# Filter2.net
KiCad netlist of a schematic drawn in Altium Designer
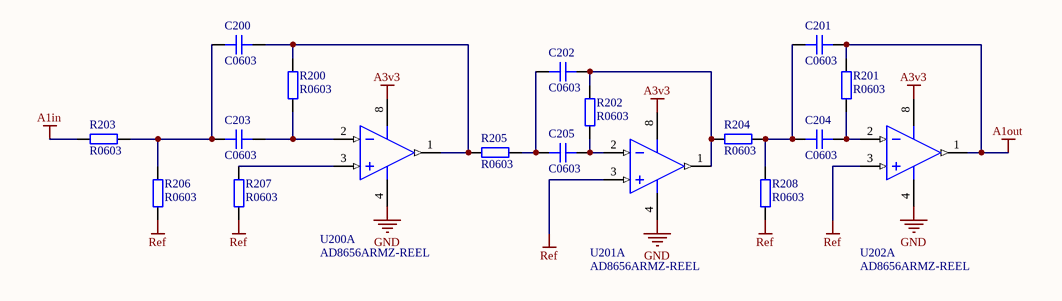
[diagram p0: Filter2.SchDoc]

(export (version "E")
  (design (tool "Eeschema 10.0.6"))
  (components
    (comp (ref "C200")
      (value "C0603")
      (footprint "CAP_0603")
      (description "Capacitor SMD 0603")
      (libsource (lib "Schematic-Lib-PhilsLab") (part "CAP_0603"))
    )
    (comp (ref "C201")
      (value "C0603")
      (footprint "CAP_0603")
      (description "Capacitor SMD 0603")
      (libsource (lib "Schematic-Lib-PhilsLab") (part "CAP_0603"))
    )
    (comp (ref "C202")
      (value "C0603")
      (footprint "CAP_0603")
      (description "Capacitor SMD 0603")
      (libsource (lib "Schematic-Lib-PhilsLab") (part "CAP_0603"))
    )
    (comp (ref "C203")
      (value "C0603")
      (footprint "CAP_0603")
      (description "Capacitor SMD 0603")
      (libsource (lib "Schematic-Lib-PhilsLab") (part "CAP_0603"))
    )
    (comp (ref "C204")
      (value "C0603")
      (footprint "CAP_0603")
      (description "Capacitor SMD 0603")
      (libsource (lib "Schematic-Lib-PhilsLab") (part "CAP_0603"))
    )
    (comp (ref "C205")
      (value "C0603")
      (footprint "CAP_0603")
      (description "Capacitor SMD 0603")
      (libsource (lib "Schematic-Lib-PhilsLab") (part "CAP_0603"))
    )
    (comp (ref "R200")
      (value "R0603")
      (footprint "RES_0603")
      (description "Resistor SMD 0603")
      (libsource (lib "Schematic-Lib-PhilsLab") (part "RES_0603"))
    )
    (comp (ref "R201")
      (value "R0603")
      (footprint "RES_0603")
      (description "Resistor SMD 0603")
      (libsource (lib "Schematic-Lib-PhilsLab") (part "RES_0603"))
    )
    (comp (ref "R202")
      (value "R0603")
      (footprint "RES_0603")
      (description "Resistor SMD 0603")
      (libsource (lib "Schematic-Lib-PhilsLab") (part "RES_0603"))
    )
    (comp (ref "R203")
      (value "R0603")
      (footprint "RES_0603")
      (description "Resistor SMD 0603")
      (libsource (lib "Schematic-Lib-PhilsLab") (part "RES_0603"))
    )
    (comp (ref "R204")
      (value "R0603")
      (footprint "RES_0603")
      (description "Resistor SMD 0603")
      (libsource (lib "Schematic-Lib-PhilsLab") (part "RES_0603"))
    )
    (comp (ref "R205")
      (value "R0603")
      (footprint "RES_0603")
      (description "Resistor SMD 0603")
      (libsource (lib "Schematic-Lib-PhilsLab") (part "RES_0603"))
    )
    (comp (ref "R206")
      (value "R0603")
      (footprint "RES_0603")
      (description "Resistor SMD 0603")
      (libsource (lib "Schematic-Lib-PhilsLab") (part "RES_0603"))
    )
    (comp (ref "R207")
      (value "R0603")
      (footprint "RES_0603")
      (description "Resistor SMD 0603")
      (libsource (lib "Schematic-Lib-PhilsLab") (part "RES_0603"))
    )
    (comp (ref "R208")
      (value "R0603")
      (footprint "RES_0603")
      (description "Resistor SMD 0603")
      (libsource (lib "Schematic-Lib-PhilsLab") (part "RES_0603"))
    )
    (comp (ref "U200")
      (value "AD8656ARMZ-REEL")
      (footprint "ADI-RM-8_N")
      (fields (field (name "GENERIC PART NUMBER") "AD8656") (field (name "MANUFACTURER") "Analog Devices"))
      (libsource (lib "Altium Content Vault") (part "ADI-OP29X-R-8"))
    )
    (comp (ref "U201")
      (value "AD8656ARMZ-REEL")
      (footprint "ADI-RM-8_N")
      (fields (field (name "GENERIC PART NUMBER") "AD8656") (field (name "MANUFACTURER") "Analog Devices"))
      (libsource (lib "Altium Content Vault") (part "ADI-OP29X-R-8"))
    )
    (comp (ref "U202")
      (value "AD8656ARMZ-REEL")
      (footprint "ADI-RM-8_N")
      (fields (field (name "GENERIC PART NUMBER") "AD8656") (field (name "MANUFACTURER") "Analog Devices"))
      (libsource (lib "Altium Content Vault") (part "ADI-OP29X-R-8"))
    )
  )
  (nets
    (net (code "1") (name "A1in") (class "Default")
      (node (ref "R203") (pin "2") (pinfunction "2_2") (pintype "passive"))
    )
    (net (code "2") (name "A1out") (class "Default")
      (node (ref "C201") (pin "2") (pinfunction "2_2") (pintype "passive"))
      (node (ref "R201") (pin "2") (pinfunction "2_2") (pintype "passive"))
      (node (ref "U202") (pin "1") (pinfunction "OUT_A_1") (pintype "output"))
    )
    (net (code "3") (name "A3v3") (class "Default")
      (node (ref "U200") (pin "8") (pinfunction "+V_8") (pintype "power_in"))
      (node (ref "U201") (pin "8") (pinfunction "+V_8") (pintype "power_in"))
      (node (ref "U202") (pin "8") (pinfunction "+V_8") (pintype "power_in"))
    )
    (net (code "4") (name "GND") (class "Default")
      (node (ref "U200") (pin "4") (pinfunction "-V_4") (pintype "power_in"))
      (node (ref "U201") (pin "4") (pinfunction "-V_4") (pintype "power_in"))
      (node (ref "U202") (pin "4") (pinfunction "-V_4") (pintype "power_in"))
    )
    (net (code "5") (name "Net-(C200-Pad1)") (class "Default")
      (node (ref "C200") (pin "1") (pinfunction "1_1") (pintype "passive"))
      (node (ref "C203") (pin "1") (pinfunction "1_1") (pintype "passive"))
      (node (ref "R203") (pin "1") (pinfunction "1_1") (pintype "passive"))
      (node (ref "R206") (pin "1") (pinfunction "1_1") (pintype "passive"))
    )
    (net (code "6") (name "Net-(C201-Pad1)") (class "Default")
      (node (ref "C201") (pin "1") (pinfunction "1_1") (pintype "passive"))
      (node (ref "C204") (pin "1") (pinfunction "1_1") (pintype "passive"))
      (node (ref "R204") (pin "1") (pinfunction "1_1") (pintype "passive"))
      (node (ref "R208") (pin "2") (pinfunction "2_2") (pintype "passive"))
    )
    (net (code "7") (name "Net-(C202-Pad1)") (class "Default")
      (node (ref "C202") (pin "1") (pinfunction "1_1") (pintype "passive"))
      (node (ref "C205") (pin "1") (pinfunction "1_1") (pintype "passive"))
      (node (ref "R205") (pin "1") (pinfunction "1_1") (pintype "passive"))
    )
    (net (code "8") (name "Net-(U200A-+IN_A)") (class "Default")
      (node (ref "R207") (pin "2") (pinfunction "2_2") (pintype "passive"))
      (node (ref "U200") (pin "3") (pinfunction "+IN_A_3") (pintype "input"))
    )
    (net (code "9") (name "Net-(U200A--IN_A)") (class "Default")
      (node (ref "C203") (pin "2") (pinfunction "2_2") (pintype "passive"))
      (node (ref "R200") (pin "1") (pinfunction "1_1") (pintype "passive"))
      (node (ref "U200") (pin "2") (pinfunction "-IN_A_2") (pintype "input"))
    )
    (net (code "10") (name "Net-(U200A-OUT_A)") (class "Default")
      (node (ref "C200") (pin "2") (pinfunction "2_2") (pintype "passive"))
      (node (ref "R200") (pin "2") (pinfunction "2_2") (pintype "passive"))
      (node (ref "R205") (pin "2") (pinfunction "2_2") (pintype "passive"))
      (node (ref "U200") (pin "1") (pinfunction "OUT_A_1") (pintype "output"))
    )
    (net (code "11") (name "Net-(U201A--IN_A)") (class "Default")
      (node (ref "C205") (pin "2") (pinfunction "2_2") (pintype "passive"))
      (node (ref "R202") (pin "1") (pinfunction "1_1") (pintype "passive"))
      (node (ref "U201") (pin "2") (pinfunction "-IN_A_2") (pintype "input"))
    )
    (net (code "12") (name "Net-(U201A-OUT_A)") (class "Default")
      (node (ref "C202") (pin "2") (pinfunction "2_2") (pintype "passive"))
      (node (ref "R202") (pin "2") (pinfunction "2_2") (pintype "passive"))
      (node (ref "R204") (pin "2") (pinfunction "2_2") (pintype "passive"))
      (node (ref "U201") (pin "1") (pinfunction "OUT_A_1") (pintype "output"))
    )
    (net (code "13") (name "Net-(U202A--IN_A)") (class "Default")
      (node (ref "C204") (pin "2") (pinfunction "2_2") (pintype "passive"))
      (node (ref "R201") (pin "1") (pinfunction "1_1") (pintype "passive"))
      (node (ref "U202") (pin "2") (pinfunction "-IN_A_2") (pintype "input"))
    )
    (net (code "14") (name "Ref") (class "Default")
      (node (ref "R206") (pin "2") (pinfunction "2_2") (pintype "passive"))
      (node (ref "R207") (pin "1") (pinfunction "1_1") (pintype "passive"))
      (node (ref "R208") (pin "1") (pinfunction "1_1") (pintype "passive"))
      (node (ref "U201") (pin "3") (pinfunction "+IN_A_3") (pintype "input"))
      (node (ref "U202") (pin "3") (pinfunction "+IN_A_3") (pintype "input"))
    )
  )
)
